# Placa_ATMEL_2019.net
KiCad netlist of a schematic drawn in EAGLE
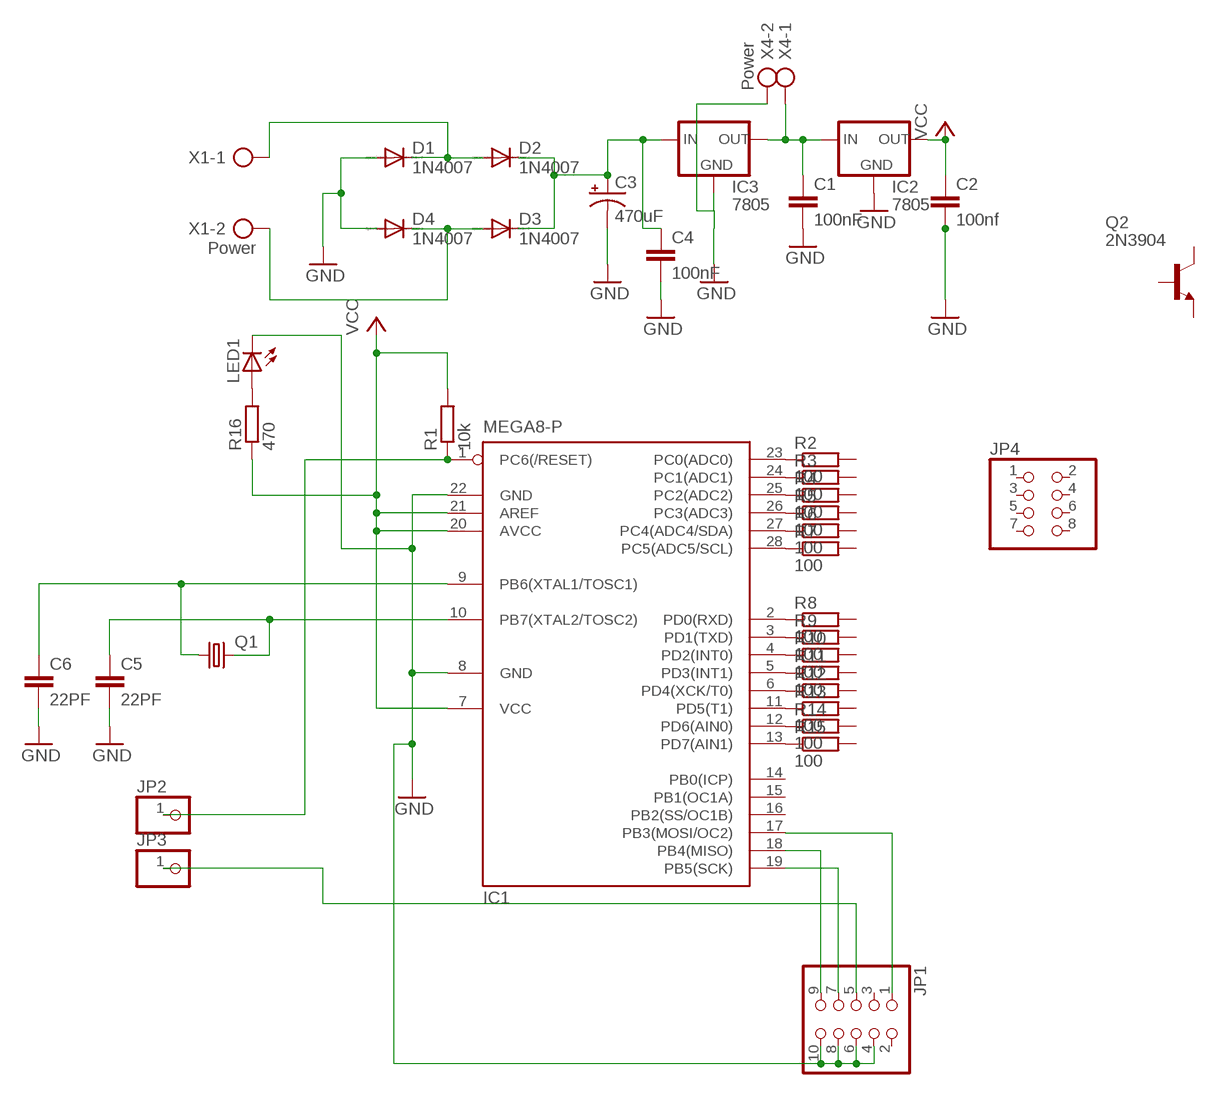
[diagram p0: schematic, sheet 1]

(export (version "E")
  (design (tool "Eeschema 10.0.6"))
  (components
    (comp (ref "C1")
      (value "100nF")
      (footprint "eagle-import:C050-025X075")
      (libsource (lib "eagle-import") (part "C-EU050-025X075"))
    )
    (comp (ref "C2")
      (value "100nf")
      (footprint "eagle-import:C050-025X075")
      (libsource (lib "eagle-import") (part "C-EU050-025X075"))
    )
    (comp (ref "C3")
      (value "470uF")
      (footprint "eagle-import:E7,5-16")
      (libsource (lib "eagle-import") (part "CPOL-USE7.5-16"))
    )
    (comp (ref "C4")
      (value "100nF")
      (footprint "eagle-import:C050-025X075")
      (libsource (lib "eagle-import") (part "C-EU050-025X075"))
    )
    (comp (ref "C5")
      (value "22PF")
      (footprint "eagle-import:C050-024X044")
      (libsource (lib "eagle-import") (part "C-EU050-024X044"))
    )
    (comp (ref "C6")
      (value "22PF")
      (footprint "eagle-import:C050-024X044")
      (libsource (lib "eagle-import") (part "C-EU050-024X044"))
    )
    (comp (ref "D1")
      (value "1N4007")
      (footprint "eagle-import:DO41-10")
      (libsource (lib "eagle-import") (part "1N4004"))
    )
    (comp (ref "D2")
      (value "1N4007")
      (footprint "eagle-import:DO41-10")
      (libsource (lib "eagle-import") (part "1N4004"))
    )
    (comp (ref "D3")
      (value "1N4007")
      (footprint "eagle-import:DO41-10")
      (libsource (lib "eagle-import") (part "1N4004"))
    )
    (comp (ref "D4")
      (value "1N4007")
      (footprint "eagle-import:DO41-10")
      (libsource (lib "eagle-import") (part "1N4004"))
    )
    (comp (ref "IC1")
      (value "MEGA8-P")
      (footprint "eagle-import:DIL28-3")
      (libsource (lib "eagle-import") (part "MEGA8-P"))
    )
    (comp (ref "IC2")
      (value "7805")
      (footprint "eagle-import:78XXL")
      (libsource (lib "eagle-import") (part "78XXL"))
    )
    (comp (ref "IC3")
      (value "7805")
      (footprint "eagle-import:78XXL")
      (libsource (lib "eagle-import") (part "78XXL"))
    )
    (comp (ref "JP1")
      (value "PINHD-2X5")
      (footprint "eagle-import:2X05")
      (libsource (lib "eagle-import") (part "PINHD-2X5"))
    )
    (comp (ref "JP2")
      (value "PINHD-1X1")
      (footprint "eagle-import:1X01")
      (libsource (lib "eagle-import") (part "PINHD-1X1"))
    )
    (comp (ref "JP3")
      (value "PINHD-1X1")
      (footprint "eagle-import:1X01")
      (libsource (lib "eagle-import") (part "PINHD-1X1"))
    )
    (comp (ref "JP4")
      (value "PINHD-2X4")
      (footprint "eagle-import:2X04")
      (libsource (lib "eagle-import") (part "PINHD-2X4"))
    )
    (comp (ref "LED1")
      (value "LED5MM")
      (footprint "eagle-import:LED5MM")
      (libsource (lib "eagle-import") (part "LED5MM"))
    )
    (comp (ref "Q1")
      (value "CRYSTALHC49S")
      (footprint "eagle-import:HC49_S")
      (libsource (lib "eagle-import") (part "CRYSTALHC49S"))
    )
    (comp (ref "Q2")
      (value "2N3904")
      (footprint "eagle-import:TO92")
      (libsource (lib "eagle-import") (part "2N3904"))
    )
    (comp (ref "R1")
      (value "10k")
      (footprint "eagle-import:0207_10")
      (libsource (lib "eagle-import") (part "R-EU_0207/10"))
    )
    (comp (ref "R2")
      (value "100")
      (footprint "eagle-import:0207_10")
      (libsource (lib "eagle-import") (part "R-EU_0207/10"))
    )
    (comp (ref "R3")
      (value "100")
      (footprint "eagle-import:0207_10")
      (libsource (lib "eagle-import") (part "R-EU_0207/10"))
    )
    (comp (ref "R4")
      (value "100")
      (footprint "eagle-import:0207_10")
      (libsource (lib "eagle-import") (part "R-EU_0207/10"))
    )
    (comp (ref "R5")
      (value "100")
      (footprint "eagle-import:0207_10")
      (libsource (lib "eagle-import") (part "R-EU_0207/10"))
    )
    (comp (ref "R6")
      (value "100")
      (footprint "eagle-import:0207_10")
      (libsource (lib "eagle-import") (part "R-EU_0207/10"))
    )
    (comp (ref "R7")
      (value "100")
      (footprint "eagle-import:0207_10")
      (libsource (lib "eagle-import") (part "R-EU_0207/10"))
    )
    (comp (ref "R8")
      (value "100")
      (footprint "eagle-import:0207_10")
      (libsource (lib "eagle-import") (part "R-EU_0207/10"))
    )
    (comp (ref "R9")
      (value "100")
      (footprint "eagle-import:0207_10")
      (libsource (lib "eagle-import") (part "R-EU_0207/10"))
    )
    (comp (ref "R10")
      (value "100")
      (footprint "eagle-import:0207_10")
      (libsource (lib "eagle-import") (part "R-EU_0207/10"))
    )
    (comp (ref "R11")
      (value "100")
      (footprint "eagle-import:0207_10")
      (libsource (lib "eagle-import") (part "R-EU_0207/10"))
    )
    (comp (ref "R12")
      (value "R-EU_0207/10")
      (footprint "eagle-import:0207_10")
      (libsource (lib "eagle-import") (part "R-EU_0207/10"))
    )
    (comp (ref "R13")
      (value "100")
      (footprint "eagle-import:0207_10")
      (libsource (lib "eagle-import") (part "R-EU_0207/10"))
    )
    (comp (ref "R14")
      (value "100")
      (footprint "eagle-import:0207_10")
      (libsource (lib "eagle-import") (part "R-EU_0207/10"))
    )
    (comp (ref "R15")
      (value "100")
      (footprint "eagle-import:0207_10")
      (libsource (lib "eagle-import") (part "R-EU_0207/10"))
    )
    (comp (ref "R16")
      (value "470")
      (footprint "eagle-import:0309_10")
      (libsource (lib "eagle-import") (part "R-EU_0309/10"))
    )
    (comp (ref "X1")
      (value "Power")
      (footprint "eagle-import:AK500_2")
      (libsource (lib "eagle-import") (part "AK500/2"))
    )
    (comp (ref "X4")
      (value "Power")
      (footprint "eagle-import:AK500_2")
      (libsource (lib "eagle-import") (part "AK500/2"))
    )
  )
  (nets
    (net (code "1") (name "GND") (class "Default")
      (node (ref "C1") (pin "2") (pinfunction "2_2") (pintype "passive"))
      (node (ref "C2") (pin "2") (pinfunction "2_2") (pintype "passive"))
      (node (ref "C3") (pin "-") (pinfunction "-_-") (pintype "passive"))
      (node (ref "C4") (pin "2") (pinfunction "2_2") (pintype "passive"))
      (node (ref "C5") (pin "2") (pinfunction "2_2") (pintype "passive"))
      (node (ref "C6") (pin "2") (pinfunction "2_2") (pintype "passive"))
      (node (ref "D1") (pin "A") (pinfunction "A_A") (pintype "passive"))
      (node (ref "D4") (pin "A") (pinfunction "A_A") (pintype "passive"))
      (node (ref "IC1") (pin "22") (pinfunction "GND_22") (pintype "power_in"))
      (node (ref "IC1") (pin "8") (pinfunction "GND_8") (pintype "power_in"))
      (node (ref "IC2") (pin "GND") (pinfunction "GND_GND") (pintype "input"))
      (node (ref "IC3") (pin "GND") (pinfunction "GND_GND") (pintype "input"))
      (node (ref "JP1") (pin "10") (pinfunction "10_10") (pintype "passive"))
      (node (ref "JP1") (pin "4") (pinfunction "4_4") (pintype "passive"))
      (node (ref "JP1") (pin "6") (pinfunction "6_6") (pintype "passive"))
      (node (ref "JP1") (pin "8") (pinfunction "8_8") (pintype "passive"))
      (node (ref "LED1") (pin "K") (pinfunction "C_K") (pintype "passive"))
      (node (ref "X4") (pin "2") (pinfunction "KL_2") (pintype "passive"))
    )
    (net (code "2") (name "Net-(C3-Pad+)") (class "Default")
      (node (ref "C3") (pin "+") (pinfunction "+_+") (pintype "passive"))
      (node (ref "C4") (pin "1") (pinfunction "1_1") (pintype "passive"))
      (node (ref "D2") (pin "C") (pinfunction "C_C") (pintype "passive"))
      (node (ref "D3") (pin "C") (pinfunction "C_C") (pintype "passive"))
      (node (ref "IC3") (pin "IN") (pinfunction "IN_IN") (pintype "input"))
    )
    (net (code "3") (name "Net-(IC1-PB3(MOSI{slash}OC2))") (class "Default")
      (node (ref "IC1") (pin "17") (pinfunction "PB3(MOSI/OC2)_17") (pintype "bidirectional"))
      (node (ref "JP1") (pin "1") (pinfunction "1_1") (pintype "passive"))
    )
    (net (code "4") (name "Net-(IC1-PB4(MISO))") (class "Default")
      (node (ref "IC1") (pin "18") (pinfunction "PB4(MISO)_18") (pintype "bidirectional"))
      (node (ref "JP1") (pin "9") (pinfunction "9_9") (pintype "passive"))
    )
    (net (code "5") (name "Net-(IC1-PB5(SCK))") (class "Default")
      (node (ref "IC1") (pin "19") (pinfunction "PB5(SCK)_19") (pintype "bidirectional"))
      (node (ref "JP1") (pin "7") (pinfunction "7_7") (pintype "passive"))
    )
    (net (code "6") (name "Net-(IC1-PB6(XTAL1{slash}TOSC1))") (class "Default")
      (node (ref "C6") (pin "1") (pinfunction "1_1") (pintype "passive"))
      (node (ref "IC1") (pin "9") (pinfunction "PB6(XTAL1/TOSC1)_9") (pintype "bidirectional"))
      (node (ref "Q1") (pin "1") (pinfunction "1_1") (pintype "passive"))
    )
    (net (code "7") (name "Net-(IC1-PB7(XTAL2{slash}TOSC2))") (class "Default")
      (node (ref "C5") (pin "1") (pinfunction "1_1") (pintype "passive"))
      (node (ref "IC1") (pin "10") (pinfunction "PB7(XTAL2/TOSC2)_10") (pintype "bidirectional"))
      (node (ref "Q1") (pin "2") (pinfunction "2_2") (pintype "passive"))
    )
    (net (code "8") (name "Net-(IC1-PC0(ADC0))") (class "Default")
      (node (ref "IC1") (pin "23") (pinfunction "PC0(ADC0)_23") (pintype "bidirectional"))
      (node (ref "R2") (pin "1") (pinfunction "1_1") (pintype "passive"))
    )
    (net (code "9") (name "Net-(IC1-PC1(ADC1))") (class "Default")
      (node (ref "IC1") (pin "24") (pinfunction "PC1(ADC1)_24") (pintype "bidirectional"))
      (node (ref "R3") (pin "1") (pinfunction "1_1") (pintype "passive"))
    )
    (net (code "10") (name "Net-(IC1-PC2(ADC2))") (class "Default")
      (node (ref "IC1") (pin "25") (pinfunction "PC2(ADC2)_25") (pintype "bidirectional"))
      (node (ref "R4") (pin "1") (pinfunction "1_1") (pintype "passive"))
    )
    (net (code "11") (name "Net-(IC1-PC3(ADC3))") (class "Default")
      (node (ref "IC1") (pin "26") (pinfunction "PC3(ADC3)_26") (pintype "bidirectional"))
      (node (ref "R5") (pin "1") (pinfunction "1_1") (pintype "passive"))
    )
    (net (code "12") (name "Net-(IC1-PC4(ADC4{slash}SDA))") (class "Default")
      (node (ref "IC1") (pin "27") (pinfunction "PC4(ADC4/SDA)_27") (pintype "bidirectional"))
      (node (ref "R6") (pin "1") (pinfunction "1_1") (pintype "passive"))
    )
    (net (code "13") (name "Net-(IC1-PC5(ADC5{slash}SCL))") (class "Default")
      (node (ref "IC1") (pin "28") (pinfunction "PC5(ADC5/SCL)_28") (pintype "bidirectional"))
      (node (ref "R7") (pin "1") (pinfunction "1_1") (pintype "passive"))
    )
    (net (code "14") (name "Net-(IC1-PC6({slash}RESET))") (class "Default")
      (node (ref "IC1") (pin "1") (pinfunction "PC6(/RESET)_1") (pintype "bidirectional"))
      (node (ref "JP2") (pin "1") (pinfunction "1_1") (pintype "passive"))
      (node (ref "R1") (pin "1") (pinfunction "1_1") (pintype "passive"))
    )
    (net (code "15") (name "Net-(IC1-PD0(RXD))") (class "Default")
      (node (ref "IC1") (pin "2") (pinfunction "PD0(RXD)_2") (pintype "bidirectional"))
      (node (ref "R8") (pin "1") (pinfunction "1_1") (pintype "passive"))
    )
    (net (code "16") (name "Net-(IC1-PD1(TXD))") (class "Default")
      (node (ref "IC1") (pin "3") (pinfunction "PD1(TXD)_3") (pintype "bidirectional"))
      (node (ref "R9") (pin "1") (pinfunction "1_1") (pintype "passive"))
    )
    (net (code "17") (name "Net-(IC1-PD2(INT0))") (class "Default")
      (node (ref "IC1") (pin "4") (pinfunction "PD2(INT0)_4") (pintype "bidirectional"))
      (node (ref "R10") (pin "1") (pinfunction "1_1") (pintype "passive"))
    )
    (net (code "18") (name "Net-(IC1-PD3(INT1))") (class "Default")
      (node (ref "IC1") (pin "5") (pinfunction "PD3(INT1)_5") (pintype "bidirectional"))
      (node (ref "R11") (pin "1") (pinfunction "1_1") (pintype "passive"))
    )
    (net (code "19") (name "Net-(IC1-PD4(XCK{slash}T0))") (class "Default")
      (node (ref "IC1") (pin "6") (pinfunction "PD4(XCK/T0)_6") (pintype "bidirectional"))
      (node (ref "R12") (pin "1") (pinfunction "1_1") (pintype "passive"))
    )
    (net (code "20") (name "Net-(IC1-PD5(T1))") (class "Default")
      (node (ref "IC1") (pin "11") (pinfunction "PD5(T1)_11") (pintype "bidirectional"))
      (node (ref "R13") (pin "1") (pinfunction "1_1") (pintype "passive"))
    )
    (net (code "21") (name "Net-(IC1-PD6(AIN0))") (class "Default")
      (node (ref "IC1") (pin "12") (pinfunction "PD6(AIN0)_12") (pintype "bidirectional"))
      (node (ref "R14") (pin "1") (pinfunction "1_1") (pintype "passive"))
    )
    (net (code "22") (name "Net-(IC1-PD7(AIN1))") (class "Default")
      (node (ref "IC1") (pin "13") (pinfunction "PD7(AIN1)_13") (pintype "bidirectional"))
      (node (ref "R15") (pin "1") (pinfunction "1_1") (pintype "passive"))
    )
    (net (code "23") (name "Net-(JP1-Pad5)") (class "Default")
      (node (ref "JP1") (pin "5") (pinfunction "5_5") (pintype "passive"))
      (node (ref "JP3") (pin "1") (pinfunction "1_1") (pintype "passive"))
    )
    (net (code "24") (name "Net-(LED1-PadA)") (class "Default")
      (node (ref "LED1") (pin "A") (pinfunction "A_A") (pintype "passive"))
      (node (ref "R16") (pin "2") (pinfunction "2_2") (pintype "passive"))
    )
    (net (code "25") (name "Net-(X1A-KL)") (class "Default")
      (node (ref "D1") (pin "C") (pinfunction "C_C") (pintype "passive"))
      (node (ref "D2") (pin "A") (pinfunction "A_A") (pintype "passive"))
      (node (ref "X1") (pin "1") (pinfunction "KL_1") (pintype "passive"))
    )
    (net (code "26") (name "Net-(X1B-KL)") (class "Default")
      (node (ref "D3") (pin "A") (pinfunction "A_A") (pintype "passive"))
      (node (ref "D4") (pin "C") (pinfunction "C_C") (pintype "passive"))
      (node (ref "X1") (pin "2") (pinfunction "KL_2") (pintype "passive"))
    )
    (net (code "27") (name "Net-(X4A-KL)") (class "Default")
      (node (ref "C1") (pin "1") (pinfunction "1_1") (pintype "passive"))
      (node (ref "IC2") (pin "IN") (pinfunction "IN_IN") (pintype "input"))
      (node (ref "IC3") (pin "OUT") (pinfunction "OUT_OUT") (pintype "passive"))
      (node (ref "X4") (pin "1") (pinfunction "KL_1") (pintype "passive"))
    )
    (net (code "28") (name "VCC") (class "Default")
      (node (ref "C2") (pin "1") (pinfunction "1_1") (pintype "passive"))
      (node (ref "IC1") (pin "20") (pinfunction "AVCC_20") (pintype "power_in"))
      (node (ref "IC1") (pin "21") (pinfunction "AREF_21") (pintype "passive"))
      (node (ref "IC1") (pin "7") (pinfunction "VCC_7") (pintype "power_in"))
      (node (ref "IC2") (pin "OUT") (pinfunction "OUT_OUT") (pintype "passive"))
      (node (ref "R1") (pin "2") (pinfunction "2_2") (pintype "passive"))
      (node (ref "R16") (pin "1") (pinfunction "1_1") (pintype "passive"))
    )
    (net (code "29") (name "unconnected-(IC1-PB0(ICP)-Pad14)") (class "Default")
      (node (ref "IC1") (pin "14") (pinfunction "PB0(ICP)_14") (pintype "bidirectional"))
    )
    (net (code "30") (name "unconnected-(IC1-PB1(OC1A)-Pad15)") (class "Default")
      (node (ref "IC1") (pin "15") (pinfunction "PB1(OC1A)_15") (pintype "bidirectional"))
    )
    (net (code "31") (name "unconnected-(IC1-PB2(SS{slash}OC1B)-Pad16)") (class "Default")
      (node (ref "IC1") (pin "16") (pinfunction "PB2(SS/OC1B)_16") (pintype "bidirectional"))
    )
    (net (code "32") (name "unconnected-(JP1-Pad2)") (class "Default")
      (node (ref "JP1") (pin "2") (pinfunction "2_2") (pintype "passive"))
    )
    (net (code "33") (name "unconnected-(JP1-Pad3)") (class "Default")
      (node (ref "JP1") (pin "3") (pinfunction "3_3") (pintype "passive"))
    )
    (net (code "34") (name "unconnected-(JP4-Pad1)") (class "Default")
      (node (ref "JP4") (pin "1") (pinfunction "1_1") (pintype "passive"))
    )
    (net (code "35") (name "unconnected-(JP4-Pad2)") (class "Default")
      (node (ref "JP4") (pin "2") (pinfunction "2_2") (pintype "passive"))
    )
    (net (code "36") (name "unconnected-(JP4-Pad3)") (class "Default")
      (node (ref "JP4") (pin "3") (pinfunction "3_3") (pintype "passive"))
    )
    (net (code "37") (name "unconnected-(JP4-Pad4)") (class "Default")
      (node (ref "JP4") (pin "4") (pinfunction "4_4") (pintype "passive"))
    )
    (net (code "38") (name "unconnected-(JP4-Pad5)") (class "Default")
      (node (ref "JP4") (pin "5") (pinfunction "5_5") (pintype "passive"))
    )
    (net (code "39") (name "unconnected-(JP4-Pad6)") (class "Default")
      (node (ref "JP4") (pin "6") (pinfunction "6_6") (pintype "passive"))
    )
    (net (code "40") (name "unconnected-(JP4-Pad7)") (class "Default")
      (node (ref "JP4") (pin "7") (pinfunction "7_7") (pintype "passive"))
    )
    (net (code "41") (name "unconnected-(JP4-Pad8)") (class "Default")
      (node (ref "JP4") (pin "8") (pinfunction "8_8") (pintype "passive"))
    )
    (net (code "42") (name "unconnected-(Q2-B-Pad2)") (class "Default")
      (node (ref "Q2") (pin "2") (pinfunction "B_2") (pintype "passive"))
    )
    (net (code "43") (name "unconnected-(Q2-C-Pad1)") (class "Default")
      (node (ref "Q2") (pin "1") (pinfunction "C_1") (pintype "passive"))
    )
    (net (code "44") (name "unconnected-(Q2-E-Pad3)") (class "Default")
      (node (ref "Q2") (pin "3") (pinfunction "E_3") (pintype "passive"))
    )
    (net (code "45") (name "unconnected-(R2-Pad2)") (class "Default")
      (node (ref "R2") (pin "2") (pinfunction "2_2") (pintype "passive"))
    )
    (net (code "46") (name "unconnected-(R3-Pad2)") (class "Default")
      (node (ref "R3") (pin "2") (pinfunction "2_2") (pintype "passive"))
    )
    (net (code "47") (name "unconnected-(R4-Pad2)") (class "Default")
      (node (ref "R4") (pin "2") (pinfunction "2_2") (pintype "passive"))
    )
    (net (code "48") (name "unconnected-(R5-Pad2)") (class "Default")
      (node (ref "R5") (pin "2") (pinfunction "2_2") (pintype "passive"))
    )
    (net (code "49") (name "unconnected-(R6-Pad2)") (class "Default")
      (node (ref "R6") (pin "2") (pinfunction "2_2") (pintype "passive"))
    )
    (net (code "50") (name "unconnected-(R7-Pad2)") (class "Default")
      (node (ref "R7") (pin "2") (pinfunction "2_2") (pintype "passive"))
    )
    (net (code "51") (name "unconnected-(R8-Pad2)") (class "Default")
      (node (ref "R8") (pin "2") (pinfunction "2_2") (pintype "passive"))
    )
    (net (code "52") (name "unconnected-(R9-Pad2)") (class "Default")
      (node (ref "R9") (pin "2") (pinfunction "2_2") (pintype "passive"))
    )
    (net (code "53") (name "unconnected-(R10-Pad2)") (class "Default")
      (node (ref "R10") (pin "2") (pinfunction "2_2") (pintype "passive"))
    )
    (net (code "54") (name "unconnected-(R11-Pad2)") (class "Default")
      (node (ref "R11") (pin "2") (pinfunction "2_2") (pintype "passive"))
    )
    (net (code "55") (name "unconnected-(R12-Pad2)") (class "Default")
      (node (ref "R12") (pin "2") (pinfunction "2_2") (pintype "passive"))
    )
    (net (code "56") (name "unconnected-(R13-Pad2)") (class "Default")
      (node (ref "R13") (pin "2") (pinfunction "2_2") (pintype "passive"))
    )
    (net (code "57") (name "unconnected-(R14-Pad2)") (class "Default")
      (node (ref "R14") (pin "2") (pinfunction "2_2") (pintype "passive"))
    )
    (net (code "58") (name "unconnected-(R15-Pad2)") (class "Default")
      (node (ref "R15") (pin "2") (pinfunction "2_2") (pintype "passive"))
    )
  )
)
